# Placa_motriz.net
KiCad netlist of a schematic drawn in EAGLE
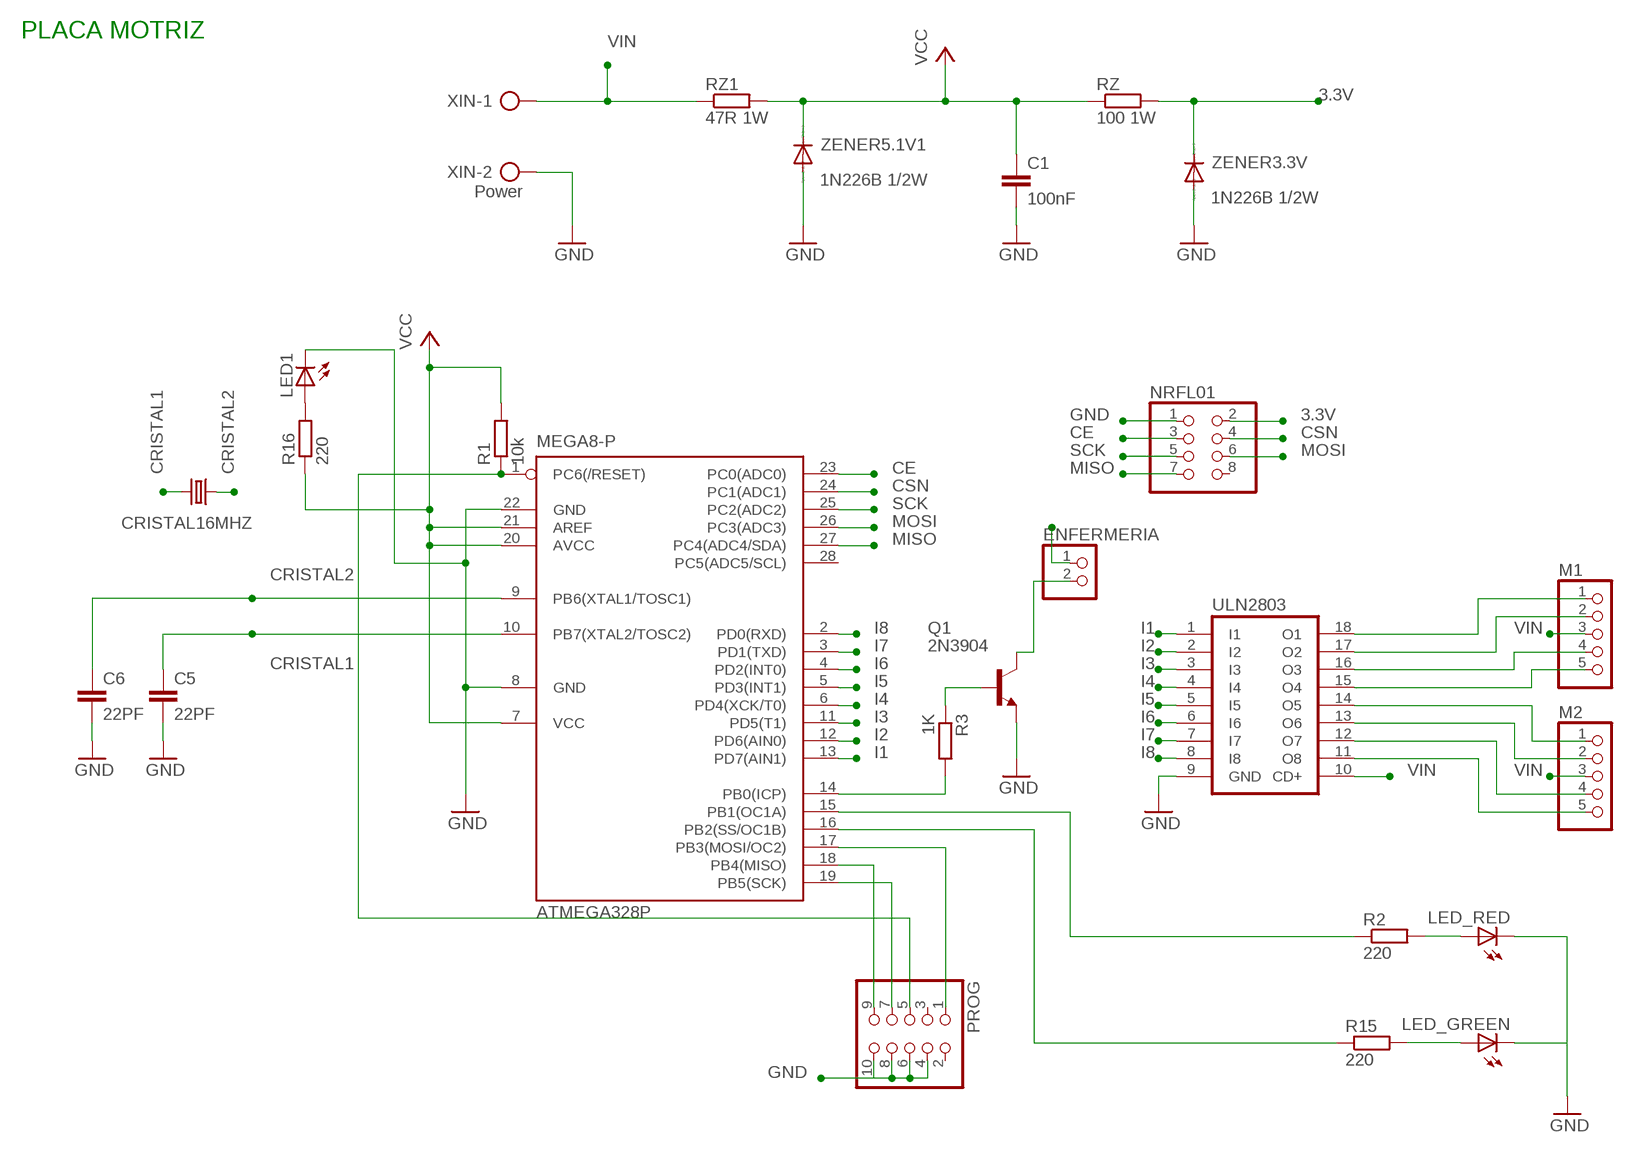
[diagram p0: schematic, sheet 1]

(export (version "E")
  (design (tool "Eeschema 10.0.6"))
  (components
    (comp (ref "ATMEGA328P")
      (value "MEGA8-P")
      (footprint "eagle-import:DIL28-3")
      (libsource (lib "eagle-import") (part "MEGA8-P"))
    )
    (comp (ref "C1")
      (value "100nF")
      (footprint "eagle-import:C050-024X044")
      (libsource (lib "eagle-import") (part "C-EU050-024X044"))
    )
    (comp (ref "C5")
      (value "22PF")
      (footprint "eagle-import:C050-024X044")
      (libsource (lib "eagle-import") (part "C-EU050-024X044"))
    )
    (comp (ref "C6")
      (value "22PF")
      (footprint "eagle-import:C050-024X044")
      (libsource (lib "eagle-import") (part "C-EU050-024X044"))
    )
    (comp (ref "CRISTAL16MHZ")
      (value "CRYSTALHC49S")
      (footprint "eagle-import:HC49_S")
      (libsource (lib "eagle-import") (part "CRYSTALHC49S"))
    )
    (comp (ref "ENFERMERIA")
      (value "PINHD-1X2")
      (footprint "eagle-import:1X02")
      (libsource (lib "eagle-import") (part "PINHD-1X2"))
    )
    (comp (ref "LED1")
      (value "LED5MM")
      (footprint "eagle-import:LED5MM")
      (libsource (lib "eagle-import") (part "LED5MM"))
    )
    (comp (ref "LED_GREEN")
      (value "LED5MM")
      (footprint "eagle-import:LED5MM")
      (libsource (lib "eagle-import") (part "LED5MM"))
    )
    (comp (ref "LED_RED")
      (value "LED5MM")
      (footprint "eagle-import:LED5MM")
      (libsource (lib "eagle-import") (part "LED5MM"))
    )
    (comp (ref "M1")
      (value "PINHD-1X5")
      (footprint "eagle-import:1X05")
      (libsource (lib "eagle-import") (part "PINHD-1X5"))
    )
    (comp (ref "M2")
      (value "PINHD-1X5")
      (footprint "eagle-import:1X05")
      (libsource (lib "eagle-import") (part "PINHD-1X5"))
    )
    (comp (ref "NRFL01")
      (value "PINHD-2X4")
      (footprint "eagle-import:2X04")
      (libsource (lib "eagle-import") (part "PINHD-2X4"))
    )
    (comp (ref "PROG")
      (value "PINHD-2X5")
      (footprint "eagle-import:2X05")
      (libsource (lib "eagle-import") (part "PINHD-2X5"))
    )
    (comp (ref "Q1")
      (value "2N3904")
      (footprint "eagle-import:TO92")
      (libsource (lib "eagle-import") (part "2N3904"))
    )
    (comp (ref "R1")
      (value "10k")
      (footprint "eagle-import:0207_15")
      (libsource (lib "eagle-import") (part "R-EU_0207/15"))
    )
    (comp (ref "R2")
      (value "220")
      (footprint "eagle-import:0207_12")
      (libsource (lib "eagle-import") (part "R-EU_0207/12"))
    )
    (comp (ref "R3")
      (value "1K")
      (footprint "eagle-import:0207_10")
      (libsource (lib "eagle-import") (part "R-EU_0207/10"))
    )
    (comp (ref "R15")
      (value "220")
      (footprint "eagle-import:0207_12")
      (libsource (lib "eagle-import") (part "R-EU_0207/12"))
    )
    (comp (ref "R16")
      (value "220")
      (footprint "eagle-import:0207_12")
      (libsource (lib "eagle-import") (part "R-EU_0207/12"))
    )
    (comp (ref "RZ")
      (value "100 1W")
      (footprint "eagle-import:0207_15")
      (libsource (lib "eagle-import") (part "R-EU_0207/15"))
    )
    (comp (ref "RZ1")
      (value "47R 1W")
      (footprint "eagle-import:0207_15")
      (libsource (lib "eagle-import") (part "R-EU_0207/15"))
    )
    (comp (ref "ULN2803")
      (value "ULN2803A")
      (footprint "eagle-import:DIL18")
      (libsource (lib "eagle-import") (part "ULN2803A"))
    )
    (comp (ref "XIN")
      (value "Power")
      (footprint "eagle-import:AK500_2")
      (libsource (lib "eagle-import") (part "AK500/2"))
    )
    (comp (ref "ZENER3.3V")
      (value "1N226B 1/2W")
      (footprint "eagle-import:DO35-10")
      (libsource (lib "eagle-import") (part "1N4148DO35-10"))
    )
    (comp (ref "ZENER5.1V1")
      (value "1N226B 1/2W")
      (footprint "eagle-import:DO35-10")
      (libsource (lib "eagle-import") (part "1N4148DO35-10"))
    )
  )
  (nets
    (net (code "1") (name "/3.3V") (class "Default")
      (node (ref "NRFL01") (pin "2") (pinfunction "2_2") (pintype "passive"))
      (node (ref "RZ") (pin "2") (pinfunction "2_2") (pintype "passive"))
      (node (ref "ZENER3.3V") (pin "C") (pinfunction "C_C") (pintype "passive"))
    )
    (net (code "2") (name "/CE") (class "Default")
      (node (ref "ATMEGA328P") (pin "23") (pinfunction "PC0(ADC0)_23") (pintype "bidirectional"))
      (node (ref "NRFL01") (pin "3") (pinfunction "3_3") (pintype "passive"))
    )
    (net (code "3") (name "/CRISTAL1") (class "Default")
      (node (ref "ATMEGA328P") (pin "10") (pinfunction "PB7(XTAL2/TOSC2)_10") (pintype "bidirectional"))
      (node (ref "C5") (pin "1") (pinfunction "1_1") (pintype "passive"))
      (node (ref "CRISTAL16MHZ") (pin "2") (pinfunction "2_2") (pintype "passive"))
    )
    (net (code "4") (name "/CRISTAL2") (class "Default")
      (node (ref "ATMEGA328P") (pin "9") (pinfunction "PB6(XTAL1/TOSC1)_9") (pintype "bidirectional"))
      (node (ref "C6") (pin "1") (pinfunction "1_1") (pintype "passive"))
      (node (ref "CRISTAL16MHZ") (pin "1") (pinfunction "1_1") (pintype "passive"))
    )
    (net (code "5") (name "/CSN") (class "Default")
      (node (ref "ATMEGA328P") (pin "24") (pinfunction "PC1(ADC1)_24") (pintype "bidirectional"))
      (node (ref "NRFL01") (pin "4") (pinfunction "4_4") (pintype "passive"))
    )
    (net (code "6") (name "/I1") (class "Default")
      (node (ref "ATMEGA328P") (pin "13") (pinfunction "PD7(AIN1)_13") (pintype "bidirectional"))
      (node (ref "ULN2803") (pin "1") (pinfunction "I1_1") (pintype "input"))
    )
    (net (code "7") (name "/I2") (class "Default")
      (node (ref "ATMEGA328P") (pin "12") (pinfunction "PD6(AIN0)_12") (pintype "bidirectional"))
      (node (ref "ULN2803") (pin "2") (pinfunction "I2_2") (pintype "input"))
    )
    (net (code "8") (name "/I3") (class "Default")
      (node (ref "ATMEGA328P") (pin "11") (pinfunction "PD5(T1)_11") (pintype "bidirectional"))
      (node (ref "ULN2803") (pin "3") (pinfunction "I3_3") (pintype "input"))
    )
    (net (code "9") (name "/I4") (class "Default")
      (node (ref "ATMEGA328P") (pin "6") (pinfunction "PD4(XCK/T0)_6") (pintype "bidirectional"))
      (node (ref "ULN2803") (pin "4") (pinfunction "I4_4") (pintype "input"))
    )
    (net (code "10") (name "/I5") (class "Default")
      (node (ref "ATMEGA328P") (pin "5") (pinfunction "PD3(INT1)_5") (pintype "bidirectional"))
      (node (ref "ULN2803") (pin "5") (pinfunction "I5_5") (pintype "input"))
    )
    (net (code "11") (name "/I6") (class "Default")
      (node (ref "ATMEGA328P") (pin "4") (pinfunction "PD2(INT0)_4") (pintype "bidirectional"))
      (node (ref "ULN2803") (pin "6") (pinfunction "I6_6") (pintype "input"))
    )
    (net (code "12") (name "/I7") (class "Default")
      (node (ref "ATMEGA328P") (pin "3") (pinfunction "PD1(TXD)_3") (pintype "bidirectional"))
      (node (ref "ULN2803") (pin "7") (pinfunction "I7_7") (pintype "input"))
    )
    (net (code "13") (name "/I8") (class "Default")
      (node (ref "ATMEGA328P") (pin "2") (pinfunction "PD0(RXD)_2") (pintype "bidirectional"))
      (node (ref "ULN2803") (pin "8") (pinfunction "I8_8") (pintype "input"))
    )
    (net (code "14") (name "/MISO") (class "Default")
      (node (ref "ATMEGA328P") (pin "27") (pinfunction "PC4(ADC4/SDA)_27") (pintype "bidirectional"))
      (node (ref "NRFL01") (pin "7") (pinfunction "7_7") (pintype "passive"))
    )
    (net (code "15") (name "/MOSI") (class "Default")
      (node (ref "ATMEGA328P") (pin "26") (pinfunction "PC3(ADC3)_26") (pintype "bidirectional"))
      (node (ref "NRFL01") (pin "6") (pinfunction "6_6") (pintype "passive"))
    )
    (net (code "16") (name "/SCK") (class "Default")
      (node (ref "ATMEGA328P") (pin "25") (pinfunction "PC2(ADC2)_25") (pintype "bidirectional"))
      (node (ref "NRFL01") (pin "5") (pinfunction "5_5") (pintype "passive"))
    )
    (net (code "17") (name "/VIN") (class "Default")
      (node (ref "ENFERMERIA") (pin "1") (pinfunction "1_1") (pintype "passive"))
      (node (ref "M1") (pin "3") (pinfunction "3_3") (pintype "passive"))
      (node (ref "M2") (pin "3") (pinfunction "3_3") (pintype "passive"))
      (node (ref "RZ1") (pin "1") (pinfunction "1_1") (pintype "passive"))
      (node (ref "ULN2803") (pin "10") (pinfunction "CD+_10") (pintype "passive"))
      (node (ref "XIN") (pin "1") (pinfunction "KL_1") (pintype "passive"))
    )
    (net (code "18") (name "GND") (class "Default")
      (node (ref "ATMEGA328P") (pin "22") (pinfunction "GND_22") (pintype "power_in"))
      (node (ref "ATMEGA328P") (pin "8") (pinfunction "GND_8") (pintype "power_in"))
      (node (ref "C1") (pin "2") (pinfunction "2_2") (pintype "passive"))
      (node (ref "C5") (pin "2") (pinfunction "2_2") (pintype "passive"))
      (node (ref "C6") (pin "2") (pinfunction "2_2") (pintype "passive"))
      (node (ref "LED1") (pin "K") (pinfunction "C_K") (pintype "passive"))
      (node (ref "LED_GREEN") (pin "K") (pinfunction "C_K") (pintype "passive"))
      (node (ref "LED_RED") (pin "K") (pinfunction "C_K") (pintype "passive"))
      (node (ref "NRFL01") (pin "1") (pinfunction "1_1") (pintype "passive"))
      (node (ref "PROG") (pin "10") (pinfunction "10_10") (pintype "passive"))
      (node (ref "PROG") (pin "4") (pinfunction "4_4") (pintype "passive"))
      (node (ref "PROG") (pin "6") (pinfunction "6_6") (pintype "passive"))
      (node (ref "PROG") (pin "8") (pinfunction "8_8") (pintype "passive"))
      (node (ref "Q1") (pin "3") (pinfunction "E_3") (pintype "passive"))
      (node (ref "ULN2803") (pin "9") (pinfunction "GND_9") (pintype "power_in"))
      (node (ref "XIN") (pin "2") (pinfunction "KL_2") (pintype "passive"))
      (node (ref "ZENER3.3V") (pin "A") (pinfunction "A_A") (pintype "passive"))
      (node (ref "ZENER5.1V1") (pin "A") (pinfunction "A_A") (pintype "passive"))
    )
    (net (code "19") (name "Net-(ATMEGA328P-PB0(ICP))") (class "Default")
      (node (ref "ATMEGA328P") (pin "14") (pinfunction "PB0(ICP)_14") (pintype "bidirectional"))
      (node (ref "R3") (pin "2") (pinfunction "2_2") (pintype "passive"))
    )
    (net (code "20") (name "Net-(ATMEGA328P-PB1(OC1A))") (class "Default")
      (node (ref "ATMEGA328P") (pin "15") (pinfunction "PB1(OC1A)_15") (pintype "bidirectional"))
      (node (ref "R2") (pin "1") (pinfunction "1_1") (pintype "passive"))
    )
    (net (code "21") (name "Net-(ATMEGA328P-PB2(SS{slash}OC1B))") (class "Default")
      (node (ref "ATMEGA328P") (pin "16") (pinfunction "PB2(SS/OC1B)_16") (pintype "bidirectional"))
      (node (ref "R15") (pin "1") (pinfunction "1_1") (pintype "passive"))
    )
    (net (code "22") (name "Net-(ATMEGA328P-PB3(MOSI{slash}OC2))") (class "Default")
      (node (ref "ATMEGA328P") (pin "17") (pinfunction "PB3(MOSI/OC2)_17") (pintype "bidirectional"))
      (node (ref "PROG") (pin "1") (pinfunction "1_1") (pintype "passive"))
    )
    (net (code "23") (name "Net-(ATMEGA328P-PB4(MISO))") (class "Default")
      (node (ref "ATMEGA328P") (pin "18") (pinfunction "PB4(MISO)_18") (pintype "bidirectional"))
      (node (ref "PROG") (pin "9") (pinfunction "9_9") (pintype "passive"))
    )
    (net (code "24") (name "Net-(ATMEGA328P-PB5(SCK))") (class "Default")
      (node (ref "ATMEGA328P") (pin "19") (pinfunction "PB5(SCK)_19") (pintype "bidirectional"))
      (node (ref "PROG") (pin "7") (pinfunction "7_7") (pintype "passive"))
    )
    (net (code "25") (name "Net-(ATMEGA328P-PC6({slash}RESET))") (class "Default")
      (node (ref "ATMEGA328P") (pin "1") (pinfunction "PC6(/RESET)_1") (pintype "bidirectional"))
      (node (ref "PROG") (pin "5") (pinfunction "5_5") (pintype "passive"))
      (node (ref "R1") (pin "1") (pinfunction "1_1") (pintype "passive"))
    )
    (net (code "26") (name "Net-(LED1-PadA)") (class "Default")
      (node (ref "LED1") (pin "A") (pinfunction "A_A") (pintype "passive"))
      (node (ref "R16") (pin "2") (pinfunction "2_2") (pintype "passive"))
    )
    (net (code "27") (name "Net-(LED_GREEN-PadA)") (class "Default")
      (node (ref "LED_GREEN") (pin "A") (pinfunction "A_A") (pintype "passive"))
      (node (ref "R15") (pin "2") (pinfunction "2_2") (pintype "passive"))
    )
    (net (code "28") (name "Net-(LED_RED-PadA)") (class "Default")
      (node (ref "LED_RED") (pin "A") (pinfunction "A_A") (pintype "passive"))
      (node (ref "R2") (pin "2") (pinfunction "2_2") (pintype "passive"))
    )
    (net (code "29") (name "Net-(Q1-B)") (class "Default")
      (node (ref "Q1") (pin "2") (pinfunction "B_2") (pintype "passive"))
      (node (ref "R3") (pin "1") (pinfunction "1_1") (pintype "passive"))
    )
    (net (code "30") (name "Net-(Q1-C)") (class "Default")
      (node (ref "ENFERMERIA") (pin "2") (pinfunction "2_2") (pintype "passive"))
      (node (ref "Q1") (pin "1") (pinfunction "C_1") (pintype "passive"))
    )
    (net (code "31") (name "Net-(ULN2803-O1)") (class "Default")
      (node (ref "M1") (pin "1") (pinfunction "1_1") (pintype "passive"))
      (node (ref "ULN2803") (pin "18") (pinfunction "O1_18") (pintype "open_collector"))
    )
    (net (code "32") (name "Net-(ULN2803-O2)") (class "Default")
      (node (ref "M1") (pin "2") (pinfunction "2_2") (pintype "passive"))
      (node (ref "ULN2803") (pin "17") (pinfunction "O2_17") (pintype "open_collector"))
    )
    (net (code "33") (name "Net-(ULN2803-O3)") (class "Default")
      (node (ref "M1") (pin "4") (pinfunction "4_4") (pintype "passive"))
      (node (ref "ULN2803") (pin "16") (pinfunction "O3_16") (pintype "open_collector"))
    )
    (net (code "34") (name "Net-(ULN2803-O4)") (class "Default")
      (node (ref "M1") (pin "5") (pinfunction "5_5") (pintype "passive"))
      (node (ref "ULN2803") (pin "15") (pinfunction "O4_15") (pintype "open_collector"))
    )
    (net (code "35") (name "Net-(ULN2803-O5)") (class "Default")
      (node (ref "M2") (pin "1") (pinfunction "1_1") (pintype "passive"))
      (node (ref "ULN2803") (pin "14") (pinfunction "O5_14") (pintype "open_collector"))
    )
    (net (code "36") (name "Net-(ULN2803-O6)") (class "Default")
      (node (ref "M2") (pin "2") (pinfunction "2_2") (pintype "passive"))
      (node (ref "ULN2803") (pin "13") (pinfunction "O6_13") (pintype "open_collector"))
    )
    (net (code "37") (name "Net-(ULN2803-O7)") (class "Default")
      (node (ref "M2") (pin "4") (pinfunction "4_4") (pintype "passive"))
      (node (ref "ULN2803") (pin "12") (pinfunction "O7_12") (pintype "open_collector"))
    )
    (net (code "38") (name "Net-(ULN2803-O8)") (class "Default")
      (node (ref "M2") (pin "5") (pinfunction "5_5") (pintype "passive"))
      (node (ref "ULN2803") (pin "11") (pinfunction "O8_11") (pintype "open_collector"))
    )
    (net (code "39") (name "VCC") (class "Default")
      (node (ref "ATMEGA328P") (pin "20") (pinfunction "AVCC_20") (pintype "power_in"))
      (node (ref "ATMEGA328P") (pin "21") (pinfunction "AREF_21") (pintype "passive"))
      (node (ref "ATMEGA328P") (pin "7") (pinfunction "VCC_7") (pintype "power_in"))
      (node (ref "C1") (pin "1") (pinfunction "1_1") (pintype "passive"))
      (node (ref "R1") (pin "2") (pinfunction "2_2") (pintype "passive"))
      (node (ref "R16") (pin "1") (pinfunction "1_1") (pintype "passive"))
      (node (ref "RZ") (pin "1") (pinfunction "1_1") (pintype "passive"))
      (node (ref "RZ1") (pin "2") (pinfunction "2_2") (pintype "passive"))
      (node (ref "ZENER5.1V1") (pin "C") (pinfunction "C_C") (pintype "passive"))
    )
    (net (code "40") (name "unconnected-(ATMEGA328P-PC5(ADC5{slash}SCL)-Pad28)") (class "Default")
      (node (ref "ATMEGA328P") (pin "28") (pinfunction "PC5(ADC5/SCL)_28") (pintype "bidirectional"))
    )
    (net (code "41") (name "unconnected-(NRFL01-Pad8)") (class "Default")
      (node (ref "NRFL01") (pin "8") (pinfunction "8_8") (pintype "passive"))
    )
    (net (code "42") (name "unconnected-(PROG-Pad2)") (class "Default")
      (node (ref "PROG") (pin "2") (pinfunction "2_2") (pintype "passive"))
    )
    (net (code "43") (name "unconnected-(PROG-Pad3)") (class "Default")
      (node (ref "PROG") (pin "3") (pinfunction "3_3") (pintype "passive"))
    )
  )
)
